# THREE_PHASE_METER.net
KiCad netlist of a schematic drawn in Altium Designer
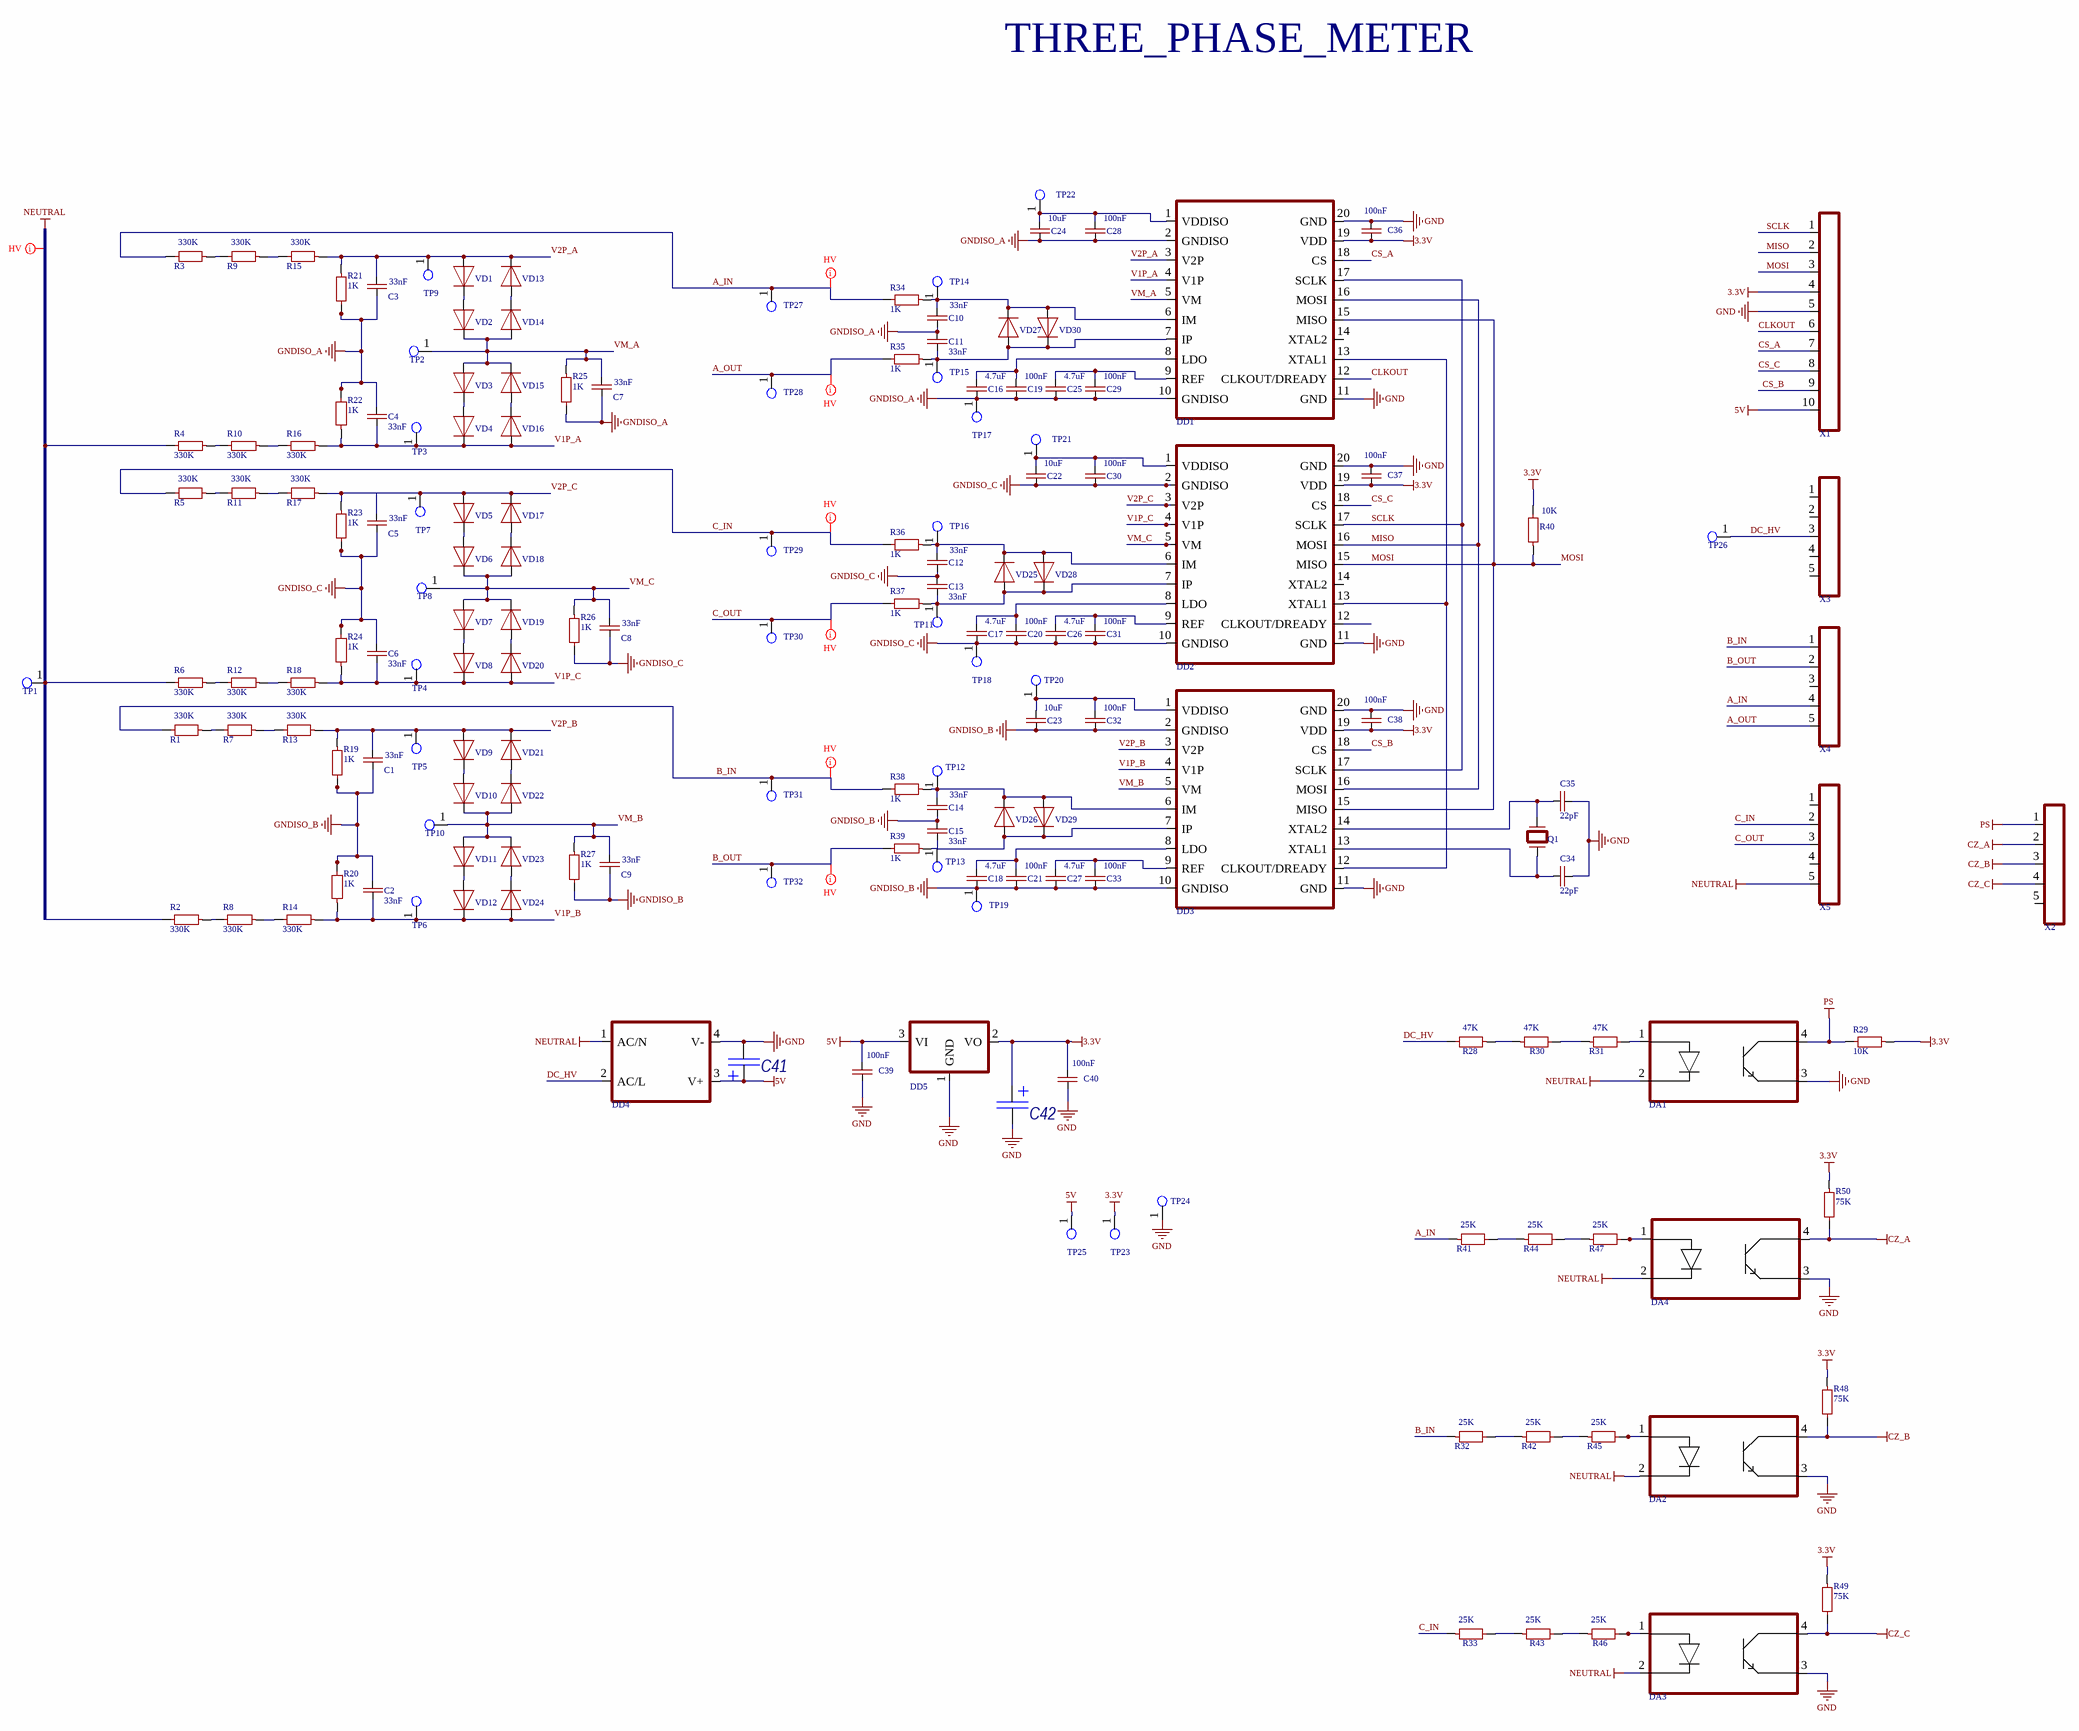
[diagram p0: THREE_PHASE_METER.SchDoc]

(export (version "E")
  (design (tool "Eeschema 10.0.6"))
  (components
    (comp (ref "C1")
      (value "33nF")
      (footprint "CAP-1206")
      (libsource (lib "PASSIVE_COMPONENTS") (part "CAP-NON-POLAR"))
    )
    (comp (ref "C2")
      (value "33nF")
      (footprint "CAP-1206")
      (libsource (lib "PASSIVE_COMPONENTS") (part "CAP-NON-POLAR"))
    )
    (comp (ref "C3")
      (value "33nF")
      (footprint "CAP-1206")
      (libsource (lib "PASSIVE_COMPONENTS") (part "CAP-NON-POLAR"))
    )
    (comp (ref "C4")
      (value "33nF")
      (footprint "CAP-1206")
      (libsource (lib "PASSIVE_COMPONENTS") (part "CAP-NON-POLAR"))
    )
    (comp (ref "C5")
      (value "33nF")
      (footprint "CAP-1206")
      (libsource (lib "PASSIVE_COMPONENTS") (part "CAP-NON-POLAR"))
    )
    (comp (ref "C6")
      (value "33nF")
      (footprint "CAP-1206")
      (libsource (lib "PASSIVE_COMPONENTS") (part "CAP-NON-POLAR"))
    )
    (comp (ref "C7")
      (value "33nF")
      (footprint "CAP-1206")
      (libsource (lib "PASSIVE_COMPONENTS") (part "CAP-NON-POLAR"))
    )
    (comp (ref "C8")
      (value "33nF")
      (footprint "CAP-1206")
      (libsource (lib "PASSIVE_COMPONENTS") (part "CAP-NON-POLAR"))
    )
    (comp (ref "C9")
      (value "33nF")
      (footprint "CAP-1206")
      (libsource (lib "PASSIVE_COMPONENTS") (part "CAP-NON-POLAR"))
    )
    (comp (ref "C10")
      (value "33nF")
      (footprint "CAP-1206")
      (libsource (lib "PASSIVE_COMPONENTS") (part "CAP-NON-POLAR"))
    )
    (comp (ref "C11")
      (value "33nF")
      (footprint "CAP-1206")
      (libsource (lib "PASSIVE_COMPONENTS") (part "CAP-NON-POLAR"))
    )
    (comp (ref "C12")
      (value "33nF")
      (footprint "CAP-1206")
      (libsource (lib "PASSIVE_COMPONENTS") (part "CAP-NON-POLAR"))
    )
    (comp (ref "C13")
      (value "33nF")
      (footprint "CAP-1206")
      (libsource (lib "PASSIVE_COMPONENTS") (part "CAP-NON-POLAR"))
    )
    (comp (ref "C14")
      (value "33nF")
      (footprint "CAP-1206")
      (libsource (lib "PASSIVE_COMPONENTS") (part "CAP-NON-POLAR"))
    )
    (comp (ref "C15")
      (value "33nF")
      (footprint "CAP-1206")
      (libsource (lib "PASSIVE_COMPONENTS") (part "CAP-NON-POLAR"))
    )
    (comp (ref "C16")
      (value "4.7uF")
      (footprint "CAP-1206")
      (libsource (lib "PASSIVE_COMPONENTS") (part "CAP-NON-POLAR"))
    )
    (comp (ref "C17")
      (value "4.7uF")
      (footprint "CAP-1206")
      (libsource (lib "PASSIVE_COMPONENTS") (part "CAP-NON-POLAR"))
    )
    (comp (ref "C18")
      (value "4.7uF")
      (footprint "CAP-1206")
      (libsource (lib "PASSIVE_COMPONENTS") (part "CAP-NON-POLAR"))
    )
    (comp (ref "C19")
      (value "100nF")
      (footprint "CAP-0603")
      (libsource (lib "PASSIVE_COMPONENTS") (part "CAP-NON-POLAR"))
    )
    (comp (ref "C20")
      (value "100nF")
      (footprint "CAP-0603")
      (libsource (lib "PASSIVE_COMPONENTS") (part "CAP-NON-POLAR"))
    )
    (comp (ref "C21")
      (value "100nF")
      (footprint "CAP-0603")
      (libsource (lib "PASSIVE_COMPONENTS") (part "CAP-NON-POLAR"))
    )
    (comp (ref "C22")
      (value "10uF")
      (footprint "CAP-1206")
      (libsource (lib "PASSIVE_COMPONENTS") (part "CAP-NON-POLAR"))
    )
    (comp (ref "C23")
      (value "10uF")
      (footprint "CAP-1206")
      (libsource (lib "PASSIVE_COMPONENTS") (part "CAP-NON-POLAR"))
    )
    (comp (ref "C24")
      (value "10uF")
      (footprint "CAP-1206")
      (libsource (lib "PASSIVE_COMPONENTS") (part "CAP-NON-POLAR"))
    )
    (comp (ref "C25")
      (value "4.7uF")
      (footprint "CAP-1206")
      (libsource (lib "PASSIVE_COMPONENTS") (part "CAP-NON-POLAR"))
    )
    (comp (ref "C26")
      (value "4.7uF")
      (footprint "CAP-1206")
      (libsource (lib "PASSIVE_COMPONENTS") (part "CAP-NON-POLAR"))
    )
    (comp (ref "C27")
      (value "4.7uF")
      (footprint "CAP-1206")
      (libsource (lib "PASSIVE_COMPONENTS") (part "CAP-NON-POLAR"))
    )
    (comp (ref "C28")
      (value "100nF")
      (footprint "CAP-0603")
      (libsource (lib "PASSIVE_COMPONENTS") (part "CAP-NON-POLAR"))
    )
    (comp (ref "C29")
      (value "100nF")
      (footprint "CAP-0603")
      (libsource (lib "PASSIVE_COMPONENTS") (part "CAP-NON-POLAR"))
    )
    (comp (ref "C30")
      (value "100nF")
      (footprint "CAP-0603")
      (libsource (lib "PASSIVE_COMPONENTS") (part "CAP-NON-POLAR"))
    )
    (comp (ref "C31")
      (value "100nF")
      (footprint "CAP-0603")
      (libsource (lib "PASSIVE_COMPONENTS") (part "CAP-NON-POLAR"))
    )
    (comp (ref "C32")
      (value "100nF")
      (footprint "CAP-0603")
      (libsource (lib "PASSIVE_COMPONENTS") (part "CAP-NON-POLAR"))
    )
    (comp (ref "C33")
      (value "100nF")
      (footprint "CAP-0603")
      (libsource (lib "PASSIVE_COMPONENTS") (part "CAP-NON-POLAR"))
    )
    (comp (ref "C34")
      (value "22pF")
      (footprint "CAP-0603")
      (libsource (lib "PASSIVE_COMPONENTS") (part "CAP-NON-POLAR"))
    )
    (comp (ref "C35")
      (value "22pF")
      (footprint "CAP-0603")
      (libsource (lib "PASSIVE_COMPONENTS") (part "CAP-NON-POLAR"))
    )
    (comp (ref "C36")
      (value "100nF")
      (footprint "CAP-0603")
      (libsource (lib "PASSIVE_COMPONENTS") (part "CAP-NON-POLAR"))
    )
    (comp (ref "C37")
      (value "100nF")
      (footprint "CAP-0603")
      (libsource (lib "PASSIVE_COMPONENTS") (part "CAP-NON-POLAR"))
    )
    (comp (ref "C38")
      (value "100nF")
      (footprint "CAP-0603")
      (libsource (lib "PASSIVE_COMPONENTS") (part "CAP-NON-POLAR"))
    )
    (comp (ref "C39")
      (value "100nF")
      (footprint "CAP-0603")
      (libsource (lib "PASSIVE_COMPONENTS") (part "CAP-NON-POLAR"))
    )
    (comp (ref "C40")
      (value "100nF")
      (footprint "CAP-0603")
      (libsource (lib "PASSIVE_COMPONENTS") (part "CAP-NON-POLAR"))
    )
    (comp (ref "C41")
      (value "~")
      (footprint "CAPAE9185X108M")
      (description "Конденсатор электролитический SMD")
      (libsource (lib "Capacitor") (part "CAPAE9185X108M"))
    )
    (comp (ref "C42")
      (value "~")
      (footprint "CAPAE9185X108M")
      (description "Конденсатор электролитический SMD")
      (libsource (lib "Capacitor") (part "CAPAE9185X108M"))
    )
    (comp (ref "DA1") (value "PC817") (footprint "4-SMD") (libsource (lib "PC817") (part "PC817")))
    (comp (ref "DA2") (value "PC817") (footprint "4-SMD") (libsource (lib "PC817") (part "PC817")))
    (comp (ref "DA3") (value "PC817") (footprint "4-SMD") (libsource (lib "PC817") (part "PC817")))
    (comp (ref "DA4") (value "PC817") (footprint "4-SMD") (libsource (lib "PC817") (part "PC817")))
    (comp (ref "DD1") (value "ADE7913") (footprint "SOIC20") (libsource (lib "ADE7913") (part "ADE7913")))
    (comp (ref "DD2") (value "ADE7913") (footprint "SOIC20") (libsource (lib "ADE7913") (part "ADE7913")))
    (comp (ref "DD3") (value "ADE7913") (footprint "SOIC20") (libsource (lib "ADE7913") (part "ADE7913")))
    (comp (ref "DD4") (value "IRM-01") (footprint "IRM-01") (libsource (lib "IRM-01") (part "IRM-01")))
    (comp (ref "DD5") (value "AMS1117") (footprint "SOT-223-3") (libsource (lib "AMS1117") (part "AMS1117")))
    (comp (ref "Q1")
      (value "OSC-2-PIN")
      (footprint "OSC-QSMD12.3x4.5x4.2")
      (libsource (lib "PASSIVE_COMPONENTS") (part "OSC-2-PIN"))
    )
    (comp (ref "R1")
      (value "330K")
      (footprint "RES-1206")
      (libsource (lib "PASSIVE_COMPONENTS") (part "RES-CONST"))
    )
    (comp (ref "R2")
      (value "330K")
      (footprint "RES-1206")
      (libsource (lib "PASSIVE_COMPONENTS") (part "RES-CONST"))
    )
    (comp (ref "R3")
      (value "330K")
      (footprint "RES-1206")
      (libsource (lib "PASSIVE_COMPONENTS") (part "RES-CONST"))
    )
    (comp (ref "R4")
      (value "330K")
      (footprint "RES-1206")
      (libsource (lib "PASSIVE_COMPONENTS") (part "RES-CONST"))
    )
    (comp (ref "R5")
      (value "330K")
      (footprint "RES-1206")
      (libsource (lib "PASSIVE_COMPONENTS") (part "RES-CONST"))
    )
    (comp (ref "R6")
      (value "330K")
      (footprint "RES-1206")
      (libsource (lib "PASSIVE_COMPONENTS") (part "RES-CONST"))
    )
    (comp (ref "R7")
      (value "330K")
      (footprint "RES-1206")
      (libsource (lib "PASSIVE_COMPONENTS") (part "RES-CONST"))
    )
    (comp (ref "R8")
      (value "330K")
      (footprint "RES-1206")
      (libsource (lib "PASSIVE_COMPONENTS") (part "RES-CONST"))
    )
    (comp (ref "R9")
      (value "330K")
      (footprint "RES-1206")
      (libsource (lib "PASSIVE_COMPONENTS") (part "RES-CONST"))
    )
    (comp (ref "R10")
      (value "330K")
      (footprint "RES-1206")
      (libsource (lib "PASSIVE_COMPONENTS") (part "RES-CONST"))
    )
    (comp (ref "R11")
      (value "330K")
      (footprint "RES-1206")
      (libsource (lib "PASSIVE_COMPONENTS") (part "RES-CONST"))
    )
    (comp (ref "R12")
      (value "330K")
      (footprint "RES-1206")
      (libsource (lib "PASSIVE_COMPONENTS") (part "RES-CONST"))
    )
    (comp (ref "R13")
      (value "330K")
      (footprint "RES-1206")
      (libsource (lib "PASSIVE_COMPONENTS") (part "RES-CONST"))
    )
    (comp (ref "R14")
      (value "330K")
      (footprint "RES-1206")
      (libsource (lib "PASSIVE_COMPONENTS") (part "RES-CONST"))
    )
    (comp (ref "R15")
      (value "330K")
      (footprint "RES-1206")
      (libsource (lib "PASSIVE_COMPONENTS") (part "RES-CONST"))
    )
    (comp (ref "R16")
      (value "330K")
      (footprint "RES-1206")
      (libsource (lib "PASSIVE_COMPONENTS") (part "RES-CONST"))
    )
    (comp (ref "R17")
      (value "330K")
      (footprint "RES-1206")
      (libsource (lib "PASSIVE_COMPONENTS") (part "RES-CONST"))
    )
    (comp (ref "R18")
      (value "330K")
      (footprint "RES-1206")
      (libsource (lib "PASSIVE_COMPONENTS") (part "RES-CONST"))
    )
    (comp (ref "R19")
      (value "1K")
      (footprint "RES-1206")
      (libsource (lib "PASSIVE_COMPONENTS") (part "RES-CONST"))
    )
    (comp (ref "R20")
      (value "1K")
      (footprint "RES-1206")
      (libsource (lib "PASSIVE_COMPONENTS") (part "RES-CONST"))
    )
    (comp (ref "R21")
      (value "1K")
      (footprint "RES-1206")
      (libsource (lib "PASSIVE_COMPONENTS") (part "RES-CONST"))
    )
    (comp (ref "R22")
      (value "1K")
      (footprint "RES-1206")
      (libsource (lib "PASSIVE_COMPONENTS") (part "RES-CONST"))
    )
    (comp (ref "R23")
      (value "1K")
      (footprint "RES-1206")
      (libsource (lib "PASSIVE_COMPONENTS") (part "RES-CONST"))
    )
    (comp (ref "R24")
      (value "1K")
      (footprint "RES-1206")
      (libsource (lib "PASSIVE_COMPONENTS") (part "RES-CONST"))
    )
    (comp (ref "R25")
      (value "1K")
      (footprint "RES-1206")
      (libsource (lib "PASSIVE_COMPONENTS") (part "RES-CONST"))
    )
    (comp (ref "R26")
      (value "1K")
      (footprint "RES-1206")
      (libsource (lib "PASSIVE_COMPONENTS") (part "RES-CONST"))
    )
    (comp (ref "R27")
      (value "1K")
      (footprint "RES-1206")
      (libsource (lib "PASSIVE_COMPONENTS") (part "RES-CONST"))
    )
    (comp (ref "R28")
      (value "47K")
      (footprint "RES-1206")
      (libsource (lib "PASSIVE_COMPONENTS") (part "RES-CONST"))
    )
    (comp (ref "R29")
      (value "10K")
      (footprint "RES-0603")
      (libsource (lib "PASSIVE_COMPONENTS") (part "RES-CONST"))
    )
    (comp (ref "R30")
      (value "47K")
      (footprint "RES-1206")
      (libsource (lib "PASSIVE_COMPONENTS") (part "RES-CONST"))
    )
    (comp (ref "R31")
      (value "47K")
      (footprint "RES-1206")
      (libsource (lib "PASSIVE_COMPONENTS") (part "RES-CONST"))
    )
    (comp (ref "R32")
      (value "25K")
      (footprint "RES-1206")
      (libsource (lib "PASSIVE_COMPONENTS") (part "RES-CONST"))
    )
    (comp (ref "R33")
      (value "25K")
      (footprint "RES-1206")
      (libsource (lib "PASSIVE_COMPONENTS") (part "RES-CONST"))
    )
    (comp (ref "R34")
      (value "1K")
      (footprint "RES-1206")
      (libsource (lib "PASSIVE_COMPONENTS") (part "RES-CONST"))
    )
    (comp (ref "R35")
      (value "1K")
      (footprint "RES-1206")
      (libsource (lib "PASSIVE_COMPONENTS") (part "RES-CONST"))
    )
    (comp (ref "R36")
      (value "1K")
      (footprint "RES-1206")
      (libsource (lib "PASSIVE_COMPONENTS") (part "RES-CONST"))
    )
    (comp (ref "R37")
      (value "1K")
      (footprint "RES-1206")
      (libsource (lib "PASSIVE_COMPONENTS") (part "RES-CONST"))
    )
    (comp (ref "R38")
      (value "1K")
      (footprint "RES-1206")
      (libsource (lib "PASSIVE_COMPONENTS") (part "RES-CONST"))
    )
    (comp (ref "R39")
      (value "1K")
      (footprint "RES-1206")
      (libsource (lib "PASSIVE_COMPONENTS") (part "RES-CONST"))
    )
    (comp (ref "R40")
      (value "10K")
      (footprint "RES-0603")
      (libsource (lib "PASSIVE_COMPONENTS") (part "RES-CONST"))
    )
    (comp (ref "R41")
      (value "25K")
      (footprint "RES-1206")
      (libsource (lib "PASSIVE_COMPONENTS") (part "RES-CONST"))
    )
    (comp (ref "R42")
      (value "25K")
      (footprint "RES-1206")
      (libsource (lib "PASSIVE_COMPONENTS") (part "RES-CONST"))
    )
    (comp (ref "R43")
      (value "25K")
      (footprint "RES-1206")
      (libsource (lib "PASSIVE_COMPONENTS") (part "RES-CONST"))
    )
    (comp (ref "R44")
      (value "25K")
      (footprint "RES-1206")
      (libsource (lib "PASSIVE_COMPONENTS") (part "RES-CONST"))
    )
    (comp (ref "R45")
      (value "25K")
      (footprint "RES-1206")
      (libsource (lib "PASSIVE_COMPONENTS") (part "RES-CONST"))
    )
    (comp (ref "R46")
      (value "25K")
      (footprint "RES-1206")
      (libsource (lib "PASSIVE_COMPONENTS") (part "RES-CONST"))
    )
    (comp (ref "R47")
      (value "25K")
      (footprint "RES-1206")
      (libsource (lib "PASSIVE_COMPONENTS") (part "RES-CONST"))
    )
    (comp (ref "R48")
      (value "75K")
      (footprint "RES-0603")
      (libsource (lib "PASSIVE_COMPONENTS") (part "RES-CONST"))
    )
    (comp (ref "R49")
      (value "75K")
      (footprint "RES-0603")
      (libsource (lib "PASSIVE_COMPONENTS") (part "RES-CONST"))
    )
    (comp (ref "R50")
      (value "75K")
      (footprint "RES-0603")
      (libsource (lib "PASSIVE_COMPONENTS") (part "RES-CONST"))
    )
    (comp (ref "TP1")
      (value "Test_Point_PCB")
      (footprint "Test_Point")
      (description "Test_Point")
      (libsource (lib "Test_Point") (part "TP_PCB?"))
    )
    (comp (ref "TP2")
      (value "Test_Point_PCB")
      (footprint "Test_Point")
      (description "Test_Point")
      (libsource (lib "Test_Point") (part "TP_PCB?"))
    )
    (comp (ref "TP3")
      (value "Test_Point_PCB")
      (footprint "Test_Point")
      (description "Test_Point")
      (libsource (lib "Test_Point") (part "TP_PCB?"))
    )
    (comp (ref "TP4")
      (value "Test_Point_PCB")
      (footprint "Test_Point")
      (description "Test_Point")
      (libsource (lib "Test_Point") (part "TP_PCB?"))
    )
    (comp (ref "TP5")
      (value "Test_Point_PCB")
      (footprint "Test_Point")
      (description "Test_Point")
      (libsource (lib "Test_Point") (part "TP_PCB?"))
    )
    (comp (ref "TP6")
      (value "Test_Point_PCB")
      (footprint "Test_Point")
      (description "Test_Point")
      (libsource (lib "Test_Point") (part "TP_PCB?"))
    )
    (comp (ref "TP7")
      (value "Test_Point_PCB")
      (footprint "Test_Point")
      (description "Test_Point")
      (libsource (lib "Test_Point") (part "TP_PCB?"))
    )
    (comp (ref "TP8")
      (value "Test_Point_PCB")
      (footprint "Test_Point")
      (description "Test_Point")
      (libsource (lib "Test_Point") (part "TP_PCB?"))
    )
    (comp (ref "TP9")
      (value "Test_Point_PCB")
      (footprint "Test_Point")
      (description "Test_Point")
      (libsource (lib "Test_Point") (part "TP_PCB?"))
    )
    (comp (ref "TP10")
      (value "Test_Point_PCB")
      (footprint "Test_Point")
      (description "Test_Point")
      (libsource (lib "Test_Point") (part "TP_PCB?"))
    )
    (comp (ref "TP11")
      (value "Test_Point_PCB")
      (footprint "Test_Point")
      (description "Test_Point")
      (libsource (lib "Test_Point") (part "TP_PCB?"))
    )
    (comp (ref "TP12")
      (value "Test_Point_PCB")
      (footprint "Test_Point")
      (description "Test_Point")
      (libsource (lib "Test_Point") (part "TP_PCB?"))
    )
    (comp (ref "TP13")
      (value "Test_Point_PCB")
      (footprint "Test_Point")
      (description "Test_Point")
      (libsource (lib "Test_Point") (part "TP_PCB?"))
    )
    (comp (ref "TP14")
      (value "Test_Point_PCB")
      (footprint "Test_Point")
      (description "Test_Point")
      (libsource (lib "Test_Point") (part "TP_PCB?"))
    )
    (comp (ref "TP15")
      (value "Test_Point_PCB")
      (footprint "Test_Point")
      (description "Test_Point")
      (libsource (lib "Test_Point") (part "TP_PCB?"))
    )
    (comp (ref "TP16")
      (value "Test_Point_PCB")
      (footprint "Test_Point")
      (description "Test_Point")
      (libsource (lib "Test_Point") (part "TP_PCB?"))
    )
    (comp (ref "TP17")
      (value "Test_Point_PCB")
      (footprint "Test_Point")
      (description "Test_Point")
      (libsource (lib "Test_Point") (part "TP_PCB?"))
    )
    (comp (ref "TP18")
      (value "Test_Point_PCB")
      (footprint "Test_Point")
      (description "Test_Point")
      (libsource (lib "Test_Point") (part "TP_PCB?"))
    )
    (comp (ref "TP19")
      (value "Test_Point_PCB")
      (footprint "Test_Point")
      (description "Test_Point")
      (libsource (lib "Test_Point") (part "TP_PCB?"))
    )
    (comp (ref "TP20")
      (value "Test_Point_PCB")
      (footprint "Test_Point")
      (description "Test_Point")
      (libsource (lib "Test_Point") (part "TP_PCB?"))
    )
    (comp (ref "TP21")
      (value "Test_Point_PCB")
      (footprint "Test_Point")
      (description "Test_Point")
      (libsource (lib "Test_Point") (part "TP_PCB?"))
    )
    (comp (ref "TP22")
      (value "Test_Point_PCB")
      (footprint "Test_Point")
      (description "Test_Point")
      (libsource (lib "Test_Point") (part "TP_PCB?"))
    )
    (comp (ref "TP23")
      (value "Test_Point_PCB")
      (footprint "Test_Point")
      (description "Test_Point")
      (libsource (lib "Test_Point") (part "TP_PCB?"))
    )
    (comp (ref "TP24")
      (value "Test_Point_PCB")
      (footprint "Test_Point")
      (description "Test_Point")
      (libsource (lib "Test_Point") (part "TP_PCB?"))
    )
    (comp (ref "TP25")
      (value "Test_Point_PCB")
      (footprint "Test_Point")
      (description "Test_Point")
      (libsource (lib "Test_Point") (part "TP_PCB?"))
    )
    (comp (ref "TP26")
      (value "Test_Point_PCB")
      (footprint "Test_Point")
      (description "Test_Point")
      (libsource (lib "Test_Point") (part "TP_PCB?"))
    )
    (comp (ref "TP27")
      (value "Test_Point_PCB")
      (footprint "Test_Point")
      (description "Test_Point")
      (libsource (lib "Test_Point") (part "TP_PCB?"))
    )
    (comp (ref "TP28")
      (value "Test_Point_PCB")
      (footprint "Test_Point")
      (description "Test_Point")
      (libsource (lib "Test_Point") (part "TP_PCB?"))
    )
    (comp (ref "TP29")
      (value "Test_Point_PCB")
      (footprint "Test_Point")
      (description "Test_Point")
      (libsource (lib "Test_Point") (part "TP_PCB?"))
    )
    (comp (ref "TP30")
      (value "Test_Point_PCB")
      (footprint "Test_Point")
      (description "Test_Point")
      (libsource (lib "Test_Point") (part "TP_PCB?"))
    )
    (comp (ref "TP31")
      (value "Test_Point_PCB")
      (footprint "Test_Point")
      (description "Test_Point")
      (libsource (lib "Test_Point") (part "TP_PCB?"))
    )
    (comp (ref "TP32")
      (value "Test_Point_PCB")
      (footprint "Test_Point")
      (description "Test_Point")
      (libsource (lib "Test_Point") (part "TP_PCB?"))
    )
    (comp (ref "VD1")
      (value "DIODE")
      (footprint "DIODE-0805")
      (libsource (lib "PASSIVE_COMPONENTS") (part "DIODE"))
    )
    (comp (ref "VD2")
      (value "DIODE")
      (footprint "DIODE-0805")
      (libsource (lib "PASSIVE_COMPONENTS") (part "DIODE"))
    )
    (comp (ref "VD3")
      (value "DIODE")
      (footprint "DIODE-0805")
      (libsource (lib "PASSIVE_COMPONENTS") (part "DIODE"))
    )
    (comp (ref "VD4")
      (value "DIODE")
      (footprint "DIODE-0805")
      (libsource (lib "PASSIVE_COMPONENTS") (part "DIODE"))
    )
    (comp (ref "VD5")
      (value "DIODE")
      (footprint "DIODE-0805")
      (libsource (lib "PASSIVE_COMPONENTS") (part "DIODE"))
    )
    (comp (ref "VD6")
      (value "DIODE")
      (footprint "DIODE-0805")
      (libsource (lib "PASSIVE_COMPONENTS") (part "DIODE"))
    )
    (comp (ref "VD7")
      (value "DIODE")
      (footprint "DIODE-0805")
      (libsource (lib "PASSIVE_COMPONENTS") (part "DIODE"))
    )
    (comp (ref "VD8")
      (value "DIODE")
      (footprint "DIODE-0805")
      (libsource (lib "PASSIVE_COMPONENTS") (part "DIODE"))
    )
    (comp (ref "VD9")
      (value "DIODE")
      (footprint "DIODE-0805")
      (libsource (lib "PASSIVE_COMPONENTS") (part "DIODE"))
    )
    (comp (ref "VD10")
      (value "DIODE")
      (footprint "DIODE-0805")
      (libsource (lib "PASSIVE_COMPONENTS") (part "DIODE"))
    )
    (comp (ref "VD11")
      (value "DIODE")
      (footprint "DIODE-0805")
      (libsource (lib "PASSIVE_COMPONENTS") (part "DIODE"))
    )
    (comp (ref "VD12")
      (value "DIODE")
      (footprint "DIODE-0805")
      (libsource (lib "PASSIVE_COMPONENTS") (part "DIODE"))
    )
    (comp (ref "VD13")
      (value "DIODE")
      (footprint "DIODE-0805")
      (libsource (lib "PASSIVE_COMPONENTS") (part "DIODE"))
    )
    (comp (ref "VD14")
      (value "DIODE")
      (footprint "DIODE-0805")
      (libsource (lib "PASSIVE_COMPONENTS") (part "DIODE"))
    )
    (comp (ref "VD15")
      (value "DIODE")
      (footprint "DIODE-0805")
      (libsource (lib "PASSIVE_COMPONENTS") (part "DIODE"))
    )
    (comp (ref "VD16")
      (value "DIODE")
      (footprint "DIODE-0805")
      (libsource (lib "PASSIVE_COMPONENTS") (part "DIODE"))
    )
    (comp (ref "VD17")
      (value "DIODE")
      (footprint "DIODE-0805")
      (libsource (lib "PASSIVE_COMPONENTS") (part "DIODE"))
    )
    (comp (ref "VD18")
      (value "DIODE")
      (footprint "DIODE-0805")
      (libsource (lib "PASSIVE_COMPONENTS") (part "DIODE"))
    )
    (comp (ref "VD19")
      (value "DIODE")
      (footprint "DIODE-0805")
      (libsource (lib "PASSIVE_COMPONENTS") (part "DIODE"))
    )
    (comp (ref "VD20")
      (value "DIODE")
      (footprint "DIODE-0805")
      (libsource (lib "PASSIVE_COMPONENTS") (part "DIODE"))
    )
    (comp (ref "VD21")
      (value "DIODE")
      (footprint "DIODE-0805")
      (libsource (lib "PASSIVE_COMPONENTS") (part "DIODE"))
    )
    (comp (ref "VD22")
      (value "DIODE")
      (footprint "DIODE-0805")
      (libsource (lib "PASSIVE_COMPONENTS") (part "DIODE"))
    )
    (comp (ref "VD23")
      (value "DIODE")
      (footprint "DIODE-0805")
      (libsource (lib "PASSIVE_COMPONENTS") (part "DIODE"))
    )
    (comp (ref "VD24")
      (value "DIODE")
      (footprint "DIODE-0805")
      (libsource (lib "PASSIVE_COMPONENTS") (part "DIODE"))
    )
    (comp (ref "VD25")
      (value "DIODE")
      (footprint "DIODE-0805")
      (libsource (lib "PASSIVE_COMPONENTS") (part "DIODE"))
    )
    (comp (ref "VD26")
      (value "DIODE")
      (footprint "DIODE-0805")
      (libsource (lib "PASSIVE_COMPONENTS") (part "DIODE"))
    )
    (comp (ref "VD27")
      (value "DIODE")
      (footprint "DIODE-0805")
      (libsource (lib "PASSIVE_COMPONENTS") (part "DIODE"))
    )
    (comp (ref "VD28")
      (value "DIODE")
      (footprint "DIODE-0805")
      (libsource (lib "PASSIVE_COMPONENTS") (part "DIODE"))
    )
    (comp (ref "VD29")
      (value "DIODE")
      (footprint "DIODE-0805")
      (libsource (lib "PASSIVE_COMPONENTS") (part "DIODE"))
    )
    (comp (ref "VD30")
      (value "DIODE")
      (footprint "DIODE-0805")
      (libsource (lib "PASSIVE_COMPONENTS") (part "DIODE"))
    )
    (comp (ref "X1") (value "BH-10") (footprint "BH-10") (libsource (lib "BH-10") (part "BH-10")))
    (comp (ref "X2")
      (value "CONN-5-PIN")
      (footprint "CONN-PLS-5-2.54_2")
      (libsource (lib "PLS-5__") (part "CONN-5-PIN"))
    )
    (comp (ref "X3")
      (value "CONN-5-PIN")
      (footprint "CONN-PLS-5-2.54_2")
      (libsource (lib "PLS-5__") (part "CONN-5-PIN"))
    )
    (comp (ref "X4")
      (value "CONN-5-PIN")
      (footprint "CONN-PLS-5-2.54_2")
      (libsource (lib "PLS-5__") (part "CONN-5-PIN"))
    )
    (comp (ref "X5")
      (value "CONN-5-PIN")
      (footprint "CONN-PLS-5-2.54_2")
      (libsource (lib "PLS-5__") (part "CONN-5-PIN"))
    )
  )
  (nets
    (net (code "1") (name "/A_IN") (class "Default")
      (node (ref "R3") (pin "2") (pinfunction "2_2") (pintype "passive"))
      (node (ref "R34") (pin "2") (pinfunction "2_2") (pintype "passive"))
      (node (ref "R41") (pin "1") (pinfunction "1_1") (pintype "passive"))
      (node (ref "TP27") (pin "1") (pinfunction "G9_1") (pintype "passive"))
      (node (ref "X4") (pin "4") (pinfunction "4_4") (pintype "passive"))
    )
    (net (code "2") (name "/A_OUT") (class "Default")
      (node (ref "R35") (pin "2") (pinfunction "2_2") (pintype "passive"))
      (node (ref "TP28") (pin "1") (pinfunction "G9_1") (pintype "passive"))
      (node (ref "X4") (pin "5") (pinfunction "5_5") (pintype "passive"))
    )
    (net (code "3") (name "/B_IN") (class "Default")
      (node (ref "R1") (pin "2") (pinfunction "2_2") (pintype "passive"))
      (node (ref "R32") (pin "1") (pinfunction "1_1") (pintype "passive"))
      (node (ref "R38") (pin "2") (pinfunction "2_2") (pintype "passive"))
      (node (ref "TP31") (pin "1") (pinfunction "G9_1") (pintype "passive"))
      (node (ref "X4") (pin "1") (pinfunction "1_1") (pintype "passive"))
    )
    (net (code "4") (name "/B_OUT") (class "Default")
      (node (ref "R39") (pin "2") (pinfunction "2_2") (pintype "passive"))
      (node (ref "TP32") (pin "1") (pinfunction "G9_1") (pintype "passive"))
      (node (ref "X4") (pin "2") (pinfunction "2_2") (pintype "passive"))
    )
    (net (code "5") (name "/CLKOUT") (class "Default")
      (node (ref "DD1") (pin "12") (pinfunction "CLKOUT/DREADY_12") (pintype "passive"))
      (node (ref "X1") (pin "6") (pinfunction "6_6") (pintype "passive"))
    )
    (net (code "6") (name "/CS_A") (class "Default")
      (node (ref "DD1") (pin "18") (pinfunction "CS_18") (pintype "passive"))
      (node (ref "X1") (pin "7") (pinfunction "7_7") (pintype "passive"))
    )
    (net (code "7") (name "/CS_B") (class "Default")
      (node (ref "DD3") (pin "18") (pinfunction "CS_18") (pintype "passive"))
      (node (ref "X1") (pin "9") (pinfunction "9_9") (pintype "passive"))
    )
    (net (code "8") (name "/CS_C") (class "Default")
      (node (ref "DD2") (pin "18") (pinfunction "CS_18") (pintype "passive"))
      (node (ref "X1") (pin "8") (pinfunction "8_8") (pintype "passive"))
    )
    (net (code "9") (name "/C_IN") (class "Default")
      (node (ref "R33") (pin "1") (pinfunction "1_1") (pintype "passive"))
      (node (ref "R36") (pin "2") (pinfunction "2_2") (pintype "passive"))
      (node (ref "R5") (pin "2") (pinfunction "2_2") (pintype "passive"))
      (node (ref "TP29") (pin "1") (pinfunction "G9_1") (pintype "passive"))
      (node (ref "X5") (pin "2") (pinfunction "2_2") (pintype "passive"))
    )
    (net (code "10") (name "/C_OUT") (class "Default")
      (node (ref "R37") (pin "2") (pinfunction "2_2") (pintype "passive"))
      (node (ref "TP30") (pin "1") (pinfunction "G9_1") (pintype "passive"))
      (node (ref "X5") (pin "3") (pinfunction "3_3") (pintype "passive"))
    )
    (net (code "11") (name "/DC_HV") (class "Default")
      (node (ref "DD4") (pin "2") (pinfunction "AC/L_2") (pintype "passive"))
      (node (ref "R28") (pin "2") (pinfunction "2_2") (pintype "passive"))
      (node (ref "TP26") (pin "1") (pinfunction "G9_1") (pintype "passive"))
      (node (ref "X3") (pin "3") (pinfunction "3_3") (pintype "passive"))
    )
    (net (code "12") (name "/MISO") (class "Default")
      (node (ref "DD1") (pin "16") (pinfunction "MOSI_16") (pintype "passive"))
      (node (ref "DD2") (pin "16") (pinfunction "MOSI_16") (pintype "passive"))
      (node (ref "DD3") (pin "16") (pinfunction "MOSI_16") (pintype "passive"))
      (node (ref "X1") (pin "2") (pinfunction "2_2") (pintype "passive"))
    )
    (net (code "13") (name "/MOSI") (class "Default")
      (node (ref "DD1") (pin "15") (pinfunction "MISO_15") (pintype "passive"))
      (node (ref "DD2") (pin "15") (pinfunction "MISO_15") (pintype "passive"))
      (node (ref "DD3") (pin "15") (pinfunction "MISO_15") (pintype "passive"))
      (node (ref "R40") (pin "1") (pinfunction "1_1") (pintype "passive"))
      (node (ref "X1") (pin "3") (pinfunction "3_3") (pintype "passive"))
    )
    (net (code "14") (name "/SCLK") (class "Default")
      (node (ref "DD1") (pin "17") (pinfunction "_SCLK_17") (pintype "passive"))
      (node (ref "DD2") (pin "17") (pinfunction "_SCLK_17") (pintype "passive"))
      (node (ref "DD3") (pin "17") (pinfunction "_SCLK_17") (pintype "passive"))
      (node (ref "X1") (pin "1") (pinfunction "1_1") (pintype "passive"))
    )
    (net (code "15") (name "/V1P_A") (class "Default")
      (node (ref "C4") (pin "2") (pinfunction "2_2") (pintype "passive"))
      (node (ref "DD1") (pin "4") (pinfunction "V1P_4") (pintype "passive"))
      (node (ref "R16") (pin "1") (pinfunction "1_1") (pintype "passive"))
      (node (ref "R22") (pin "1") (pinfunction "1_1") (pintype "passive"))
      (node (ref "TP3") (pin "1") (pinfunction "G9_1") (pintype "passive"))
      (node (ref "VD16") (pin "2") (pinfunction "A_2") (pintype "passive"))
      (node (ref "VD4") (pin "1") (pinfunction "C_1") (pintype "passive"))
    )
    (net (code "16") (name "/V1P_B") (class "Default")
      (node (ref "C2") (pin "2") (pinfunction "2_2") (pintype "passive"))
      (node (ref "DD3") (pin "4") (pinfunction "V1P_4") (pintype "passive"))
      (node (ref "R14") (pin "1") (pinfunction "1_1") (pintype "passive"))
      (node (ref "R20") (pin "1") (pinfunction "1_1") (pintype "passive"))
      (node (ref "TP6") (pin "1") (pinfunction "G9_1") (pintype "passive"))
      (node (ref "VD12") (pin "1") (pinfunction "C_1") (pintype "passive"))
      (node (ref "VD24") (pin "2") (pinfunction "A_2") (pintype "passive"))
    )
    (net (code "17") (name "/V1P_C") (class "Default")
      (node (ref "C6") (pin "2") (pinfunction "2_2") (pintype "passive"))
      (node (ref "DD2") (pin "4") (pinfunction "V1P_4") (pintype "passive"))
      (node (ref "R18") (pin "1") (pinfunction "1_1") (pintype "passive"))
      (node (ref "R24") (pin "1") (pinfunction "1_1") (pintype "passive"))
      (node (ref "TP4") (pin "1") (pinfunction "G9_1") (pintype "passive"))
      (node (ref "VD20") (pin "2") (pinfunction "A_2") (pintype "passive"))
      (node (ref "VD8") (pin "1") (pinfunction "C_1") (pintype "passive"))
    )
    (net (code "18") (name "/V2P_A") (class "Default")
      (node (ref "C3") (pin "2") (pinfunction "2_2") (pintype "passive"))
      (node (ref "DD1") (pin "3") (pinfunction "V2P_3") (pintype "passive"))
      (node (ref "R15") (pin "1") (pinfunction "1_1") (pintype "passive"))
      (node (ref "R21") (pin "1") (pinfunction "1_1") (pintype "passive"))
      (node (ref "TP9") (pin "1") (pinfunction "G9_1") (pintype "passive"))
      (node (ref "VD1") (pin "2") (pinfunction "A_2") (pintype "passive"))
      (node (ref "VD13") (pin "1") (pinfunction "C_1") (pintype "passive"))
    )
    (net (code "19") (name "/V2P_B") (class "Default")
      (node (ref "C1") (pin "2") (pinfunction "2_2") (pintype "passive"))
      (node (ref "DD3") (pin "3") (pinfunction "V2P_3") (pintype "passive"))
      (node (ref "R13") (pin "1") (pinfunction "1_1") (pintype "passive"))
      (node (ref "R19") (pin "1") (pinfunction "1_1") (pintype "passive"))
      (node (ref "TP5") (pin "1") (pinfunction "G9_1") (pintype "passive"))
      (node (ref "VD21") (pin "1") (pinfunction "C_1") (pintype "passive"))
      (node (ref "VD9") (pin "2") (pinfunction "A_2") (pintype "passive"))
    )
    (net (code "20") (name "/V2P_C") (class "Default")
      (node (ref "C5") (pin "2") (pinfunction "2_2") (pintype "passive"))
      (node (ref "DD2") (pin "3") (pinfunction "V2P_3") (pintype "passive"))
      (node (ref "R17") (pin "1") (pinfunction "1_1") (pintype "passive"))
      (node (ref "R23") (pin "1") (pinfunction "1_1") (pintype "passive"))
      (node (ref "TP7") (pin "1") (pinfunction "G9_1") (pintype "passive"))
      (node (ref "VD17") (pin "1") (pinfunction "C_1") (pintype "passive"))
      (node (ref "VD5") (pin "2") (pinfunction "A_2") (pintype "passive"))
    )
    (net (code "21") (name "/VM_A") (class "Default")
      (node (ref "C7") (pin "2") (pinfunction "2_2") (pintype "passive"))
      (node (ref "DD1") (pin "5") (pinfunction "VM_5") (pintype "passive"))
      (node (ref "R25") (pin "1") (pinfunction "1_1") (pintype "passive"))
      (node (ref "TP2") (pin "1") (pinfunction "G9_1") (pintype "passive"))
      (node (ref "VD14") (pin "2") (pinfunction "A_2") (pintype "passive"))
      (node (ref "VD15") (pin "1") (pinfunction "C_1") (pintype "passive"))
      (node (ref "VD2") (pin "1") (pinfunction "C_1") (pintype "passive"))
      (node (ref "VD3") (pin "2") (pinfunction "A_2") (pintype "passive"))
    )
    (net (code "22") (name "/VM_B") (class "Default")
      (node (ref "C9") (pin "2") (pinfunction "2_2") (pintype "passive"))
      (node (ref "DD3") (pin "5") (pinfunction "VM_5") (pintype "passive"))
      (node (ref "R27") (pin "1") (pinfunction "1_1") (pintype "passive"))
      (node (ref "TP10") (pin "1") (pinfunction "G9_1") (pintype "passive"))
      (node (ref "VD10") (pin "1") (pinfunction "C_1") (pintype "passive"))
      (node (ref "VD11") (pin "2") (pinfunction "A_2") (pintype "passive"))
      (node (ref "VD22") (pin "2") (pinfunction "A_2") (pintype "passive"))
      (node (ref "VD23") (pin "1") (pinfunction "C_1") (pintype "passive"))
    )
    (net (code "23") (name "/VM_C") (class "Default")
      (node (ref "C8") (pin "2") (pinfunction "2_2") (pintype "passive"))
      (node (ref "DD2") (pin "5") (pinfunction "VM_5") (pintype "passive"))
      (node (ref "R26") (pin "1") (pinfunction "1_1") (pintype "passive"))
      (node (ref "TP8") (pin "1") (pinfunction "G9_1") (pintype "passive"))
      (node (ref "VD18") (pin "2") (pinfunction "A_2") (pintype "passive"))
      (node (ref "VD19") (pin "1") (pinfunction "C_1") (pintype "passive"))
      (node (ref "VD6") (pin "1") (pinfunction "C_1") (pintype "passive"))
      (node (ref "VD7") (pin "2") (pinfunction "A_2") (pintype "passive"))
    )
    (net (code "24") (name "3.3V") (class "Default")
      (node (ref "C36") (pin "1") (pinfunction "1_1") (pintype "passive"))
      (node (ref "C37") (pin "1") (pinfunction "1_1") (pintype "passive"))
      (node (ref "C38") (pin "1") (pinfunction "1_1") (pintype "passive"))
      (node (ref "C40") (pin "2") (pinfunction "2_2") (pintype "passive"))
      (node (ref "C42") (pin "1") (pinfunction "+_1") (pintype "passive"))
      (node (ref "DD1") (pin "19") (pinfunction "VDD_19") (pintype "passive"))
      (node (ref "DD2") (pin "19") (pinfunction "VDD_19") (pintype "passive"))
      (node (ref "DD3") (pin "19") (pinfunction "VDD_19") (pintype "passive"))
      (node (ref "DD5") (pin "2") (pinfunction "VO_2") (pintype "passive"))
      (node (ref "R29") (pin "1") (pinfunction "1_1") (pintype "passive"))
      (node (ref "R40") (pin "2") (pinfunction "2_2") (pintype "passive"))
      (node (ref "R48") (pin "1") (pinfunction "1_1") (pintype "passive"))
      (node (ref "R49") (pin "1") (pinfunction "1_1") (pintype "passive"))
      (node (ref "R50") (pin "1") (pinfunction "1_1") (pintype "passive"))
      (node (ref "TP23") (pin "1") (pinfunction "G9_1") (pintype "passive"))
      (node (ref "X1") (pin "4") (pinfunction "4_4") (pintype "passive"))
    )
    (net (code "25") (name "5V") (class "Default")
      (node (ref "C39") (pin "2") (pinfunction "2_2") (pintype "passive"))
      (node (ref "C41") (pin "1") (pinfunction "+_1") (pintype "passive"))
      (node (ref "DD4") (pin "3") (pinfunction "V+_3") (pintype "passive"))
      (node (ref "DD5") (pin "3") (pinfunction "VI_3") (pintype "passive"))
      (node (ref "TP25") (pin "1") (pinfunction "G9_1") (pintype "passive"))
      (node (ref "X1") (pin "10") (pinfunction "10_10") (pintype "passive"))
    )
    (net (code "26") (name "CZ_A") (class "Default")
      (node (ref "DA4") (pin "4") (pinfunction "COLLECTOR_4") (pintype "passive"))
      (node (ref "R50") (pin "2") (pinfunction "2_2") (pintype "passive"))
      (node (ref "X2") (pin "2") (pinfunction "2_2") (pintype "passive"))
    )
    (net (code "27") (name "CZ_B") (class "Default")
      (node (ref "DA2") (pin "4") (pinfunction "COLLECTOR_4") (pintype "passive"))
      (node (ref "R48") (pin "2") (pinfunction "2_2") (pintype "passive"))
      (node (ref "X2") (pin "3") (pinfunction "3_3") (pintype "passive"))
    )
    (net (code "28") (name "CZ_C") (class "Default")
      (node (ref "DA3") (pin "4") (pinfunction "COLLECTOR_4") (pintype "passive"))
      (node (ref "R49") (pin "2") (pinfunction "2_2") (pintype "passive"))
      (node (ref "X2") (pin "4") (pinfunction "4_4") (pintype "passive"))
    )
    (net (code "29") (name "GND") (class "Default")
      (node (ref "C34") (pin "1") (pinfunction "1_1") (pintype "passive"))
      (node (ref "C35") (pin "1") (pinfunction "1_1") (pintype "passive"))
      (node (ref "C36") (pin "2") (pinfunction "2_2") (pintype "passive"))
      (node (ref "C37") (pin "2") (pinfunction "2_2") (pintype "passive"))
      (node (ref "C38") (pin "2") (pinfunction "2_2") (pintype "passive"))
      (node (ref "C39") (pin "1") (pinfunction "1_1") (pintype "passive"))
      (node (ref "C40") (pin "1") (pinfunction "1_1") (pintype "passive"))
      (node (ref "C41") (pin "2") (pintype "passive"))
      (node (ref "C42") (pin "2") (pintype "passive"))
      (node (ref "DA1") (pin "3") (pinfunction "EMITTER_3") (pintype "passive"))
      (node (ref "DA2") (pin "3") (pinfunction "EMITTER_3") (pintype "passive"))
      (node (ref "DA3") (pin "3") (pinfunction "EMITTER_3") (pintype "passive"))
      (node (ref "DA4") (pin "3") (pinfunction "EMITTER_3") (pintype "passive"))
      (node (ref "DD1") (pin "11") (pinfunction "_GND_11") (pintype "passive"))
      (node (ref "DD1") (pin "20") (pinfunction "_GND_20") (pintype "passive"))
      (node (ref "DD2") (pin "11") (pinfunction "_GND_11") (pintype "passive"))
      (node (ref "DD2") (pin "20") (pinfunction "_GND_20") (pintype "passive"))
      (node (ref "DD3") (pin "11") (pinfunction "_GND_11") (pintype "passive"))
      (node (ref "DD3") (pin "20") (pinfunction "_GND_20") (pintype "passive"))
      (node (ref "DD4") (pin "4") (pinfunction "V-_4") (pintype "passive"))
      (node (ref "DD5") (pin "1") (pinfunction "GND_1") (pintype "passive"))
      (node (ref "TP24") (pin "1") (pinfunction "G9_1") (pintype "passive"))
      (node (ref "X1") (pin "5") (pinfunction "5_5") (pintype "passive"))
    )
    (net (code "30") (name "GNDISO_A") (class "Default")
      (node (ref "C10") (pin "1") (pinfunction "1_1") (pintype "passive"))
      (node (ref "C11") (pin "1") (pinfunction "1_1") (pintype "passive"))
      (node (ref "C16") (pin "1") (pinfunction "1_1") (pintype "passive"))
      (node (ref "C19") (pin "1") (pinfunction "1_1") (pintype "passive"))
      (node (ref "C24") (pin "1") (pinfunction "1_1") (pintype "passive"))
      (node (ref "C25") (pin "1") (pinfunction "1_1") (pintype "passive"))
      (node (ref "C28") (pin "1") (pinfunction "1_1") (pintype "passive"))
      (node (ref "C29") (pin "1") (pinfunction "1_1") (pintype "passive"))
      (node (ref "C3") (pin "1") (pinfunction "1_1") (pintype "passive"))
      (node (ref "C4") (pin "1") (pinfunction "1_1") (pintype "passive"))
      (node (ref "C7") (pin "1") (pinfunction "1_1") (pintype "passive"))
      (node (ref "DD1") (pin "10") (pinfunction "GNDISO_10") (pintype "passive"))
      (node (ref "DD1") (pin "2") (pinfunction "GNDISO_2") (pintype "passive"))
      (node (ref "R21") (pin "2") (pinfunction "2_2") (pintype "passive"))
      (node (ref "R22") (pin "2") (pinfunction "2_2") (pintype "passive"))
      (node (ref "R25") (pin "2") (pinfunction "2_2") (pintype "passive"))
      (node (ref "TP17") (pin "1") (pinfunction "G9_1") (pintype "passive"))
    )
    (net (code "31") (name "GNDISO_B") (class "Default")
      (node (ref "C1") (pin "1") (pinfunction "1_1") (pintype "passive"))
      (node (ref "C14") (pin "1") (pinfunction "1_1") (pintype "passive"))
      (node (ref "C15") (pin "1") (pinfunction "1_1") (pintype "passive"))
      (node (ref "C18") (pin "1") (pinfunction "1_1") (pintype "passive"))
      (node (ref "C2") (pin "1") (pinfunction "1_1") (pintype "passive"))
      (node (ref "C21") (pin "1") (pinfunction "1_1") (pintype "passive"))
      (node (ref "C23") (pin "1") (pinfunction "1_1") (pintype "passive"))
      (node (ref "C27") (pin "1") (pinfunction "1_1") (pintype "passive"))
      (node (ref "C32") (pin "1") (pinfunction "1_1") (pintype "passive"))
      (node (ref "C33") (pin "1") (pinfunction "1_1") (pintype "passive"))
      (node (ref "C9") (pin "1") (pinfunction "1_1") (pintype "passive"))
      (node (ref "DD3") (pin "10") (pinfunction "GNDISO_10") (pintype "passive"))
      (node (ref "DD3") (pin "2") (pinfunction "GNDISO_2") (pintype "passive"))
      (node (ref "R19") (pin "2") (pinfunction "2_2") (pintype "passive"))
      (node (ref "R20") (pin "2") (pinfunction "2_2") (pintype "passive"))
      (node (ref "R27") (pin "2") (pinfunction "2_2") (pintype "passive"))
      (node (ref "TP19") (pin "1") (pinfunction "G9_1") (pintype "passive"))
    )
    (net (code "32") (name "GNDISO_C") (class "Default")
      (node (ref "C12") (pin "1") (pinfunction "1_1") (pintype "passive"))
      (node (ref "C13") (pin "1") (pinfunction "1_1") (pintype "passive"))
      (node (ref "C17") (pin "1") (pinfunction "1_1") (pintype "passive"))
      (node (ref "C20") (pin "1") (pinfunction "1_1") (pintype "passive"))
      (node (ref "C22") (pin "1") (pinfunction "1_1") (pintype "passive"))
      (node (ref "C26") (pin "1") (pinfunction "1_1") (pintype "passive"))
      (node (ref "C30") (pin "1") (pinfunction "1_1") (pintype "passive"))
      (node (ref "C31") (pin "1") (pinfunction "1_1") (pintype "passive"))
      (node (ref "C5") (pin "1") (pinfunction "1_1") (pintype "passive"))
      (node (ref "C6") (pin "1") (pinfunction "1_1") (pintype "passive"))
      (node (ref "C8") (pin "1") (pinfunction "1_1") (pintype "passive"))
      (node (ref "DD2") (pin "10") (pinfunction "GNDISO_10") (pintype "passive"))
      (node (ref "DD2") (pin "2") (pinfunction "GNDISO_2") (pintype "passive"))
      (node (ref "R23") (pin "2") (pinfunction "2_2") (pintype "passive"))
      (node (ref "R24") (pin "2") (pinfunction "2_2") (pintype "passive"))
      (node (ref "R26") (pin "2") (pinfunction "2_2") (pintype "passive"))
      (node (ref "TP18") (pin "1") (pinfunction "G9_1") (pintype "passive"))
    )
    (net (code "33") (name "NEUTRAL") (class "Default")
      (node (ref "DA1") (pin "2") (pinfunction "CATHODE_2") (pintype "passive"))
      (node (ref "DA2") (pin "2") (pinfunction "CATHODE_2") (pintype "passive"))
      (node (ref "DA3") (pin "2") (pinfunction "CATHODE_2") (pintype "passive"))
      (node (ref "DA4") (pin "2") (pinfunction "CATHODE_2") (pintype "passive"))
      (node (ref "DD4") (pin "1") (pinfunction "AC/N_1") (pintype "passive"))
      (node (ref "R2") (pin "2") (pinfunction "2_2") (pintype "passive"))
      (node (ref "R4") (pin "2") (pinfunction "2_2") (pintype "passive"))
      (node (ref "R6") (pin "2") (pinfunction "2_2") (pintype "passive"))
      (node (ref "TP1") (pin "1") (pinfunction "G9_1") (pintype "passive"))
      (node (ref "X5") (pin "5") (pinfunction "5_5") (pintype "passive"))
    )
    (net (code "34") (name "Net-(DA1-ANODE)") (class "Default")
      (node (ref "DA1") (pin "1") (pinfunction "ANODE_1") (pintype "passive"))
      (node (ref "R31") (pin "2") (pinfunction "2_2") (pintype "passive"))
    )
    (net (code "35") (name "Net-(DA2-ANODE)") (class "Default")
      (node (ref "DA2") (pin "1") (pinfunction "ANODE_1") (pintype "passive"))
      (node (ref "R45") (pin "2") (pinfunction "2_2") (pintype "passive"))
    )
    (net (code "36") (name "Net-(DA3-ANODE)") (class "Default")
      (node (ref "DA3") (pin "1") (pinfunction "ANODE_1") (pintype "passive"))
      (node (ref "R46") (pin "2") (pinfunction "2_2") (pintype "passive"))
    )
    (net (code "37") (name "Net-(DA4-ANODE)") (class "Default")
      (node (ref "DA4") (pin "1") (pinfunction "ANODE_1") (pintype "passive"))
      (node (ref "R47") (pin "2") (pinfunction "2_2") (pintype "passive"))
    )
    (net (code "38") (name "Net-(DD1-IM)") (class "Default")
      (node (ref "C10") (pin "2") (pinfunction "2_2") (pintype "passive"))
      (node (ref "DD1") (pin "6") (pinfunction "IM_6") (pintype "passive"))
      (node (ref "R34") (pin "1") (pinfunction "1_1") (pintype "passive"))
      (node (ref "TP14") (pin "1") (pinfunction "G9_1") (pintype "passive"))
      (node (ref "VD27") (pin "1") (pinfunction "C_1") (pintype "passive"))
      (node (ref "VD30") (pin "2") (pinfunction "A_2") (pintype "passive"))
    )
    (net (code "39") (name "Net-(DD1-IP)") (class "Default")
      (node (ref "C11") (pin "2") (pinfunction "2_2") (pintype "passive"))
      (node (ref "DD1") (pin "7") (pinfunction "IP_7") (pintype "passive"))
      (node (ref "R35") (pin "1") (pinfunction "1_1") (pintype "passive"))
      (node (ref "TP15") (pin "1") (pinfunction "G9_1") (pintype "passive"))
      (node (ref "VD27") (pin "2") (pinfunction "A_2") (pintype "passive"))
      (node (ref "VD30") (pin "1") (pinfunction "C_1") (pintype "passive"))
    )
    (net (code "40") (name "Net-(DD1-LDO)") (class "Default")
      (node (ref "C16") (pin "2") (pinfunction "2_2") (pintype "passive"))
      (node (ref "C19") (pin "2") (pinfunction "2_2") (pintype "passive"))
      (node (ref "DD1") (pin "8") (pinfunction "LDO_8") (pintype "passive"))
    )
    (net (code "41") (name "Net-(DD1-REF)") (class "Default")
      (node (ref "C25") (pin "2") (pinfunction "2_2") (pintype "passive"))
      (node (ref "C29") (pin "2") (pinfunction "2_2") (pintype "passive"))
      (node (ref "DD1") (pin "9") (pinfunction "REF_9") (pintype "passive"))
    )
    (net (code "42") (name "Net-(DD1-VDDISO)") (class "Default")
      (node (ref "C24") (pin "2") (pinfunction "2_2") (pintype "passive"))
      (node (ref "C28") (pin "2") (pinfunction "2_2") (pintype "passive"))
      (node (ref "DD1") (pin "1") (pinfunction "VDDISO_1") (pintype "passive"))
      (node (ref "TP22") (pin "1") (pinfunction "G9_1") (pintype "passive"))
    )
    (net (code "43") (name "Net-(DD1-XTAL1)") (class "Default")
      (node (ref "DD1") (pin "13") (pinfunction "XTAL1_13") (pintype "passive"))
      (node (ref "DD2") (pin "13") (pinfunction "XTAL1_13") (pintype "passive"))
      (node (ref "DD3") (pin "12") (pinfunction "CLKOUT/DREADY_12") (pintype "passive"))
    )
    (net (code "44") (name "Net-(DD2-IM)") (class "Default")
      (node (ref "C12") (pin "2") (pinfunction "2_2") (pintype "passive"))
      (node (ref "DD2") (pin "6") (pinfunction "IM_6") (pintype "passive"))
      (node (ref "R36") (pin "1") (pinfunction "1_1") (pintype "passive"))
      (node (ref "TP16") (pin "1") (pinfunction "G9_1") (pintype "passive"))
      (node (ref "VD25") (pin "1") (pinfunction "C_1") (pintype "passive"))
      (node (ref "VD28") (pin "2") (pinfunction "A_2") (pintype "passive"))
    )
    (net (code "45") (name "Net-(DD2-IP)") (class "Default")
      (node (ref "C13") (pin "2") (pinfunction "2_2") (pintype "passive"))
      (node (ref "DD2") (pin "7") (pinfunction "IP_7") (pintype "passive"))
      (node (ref "R37") (pin "1") (pinfunction "1_1") (pintype "passive"))
      (node (ref "TP11") (pin "1") (pinfunction "G9_1") (pintype "passive"))
      (node (ref "VD25") (pin "2") (pinfunction "A_2") (pintype "passive"))
      (node (ref "VD28") (pin "1") (pinfunction "C_1") (pintype "passive"))
    )
    (net (code "46") (name "Net-(DD2-LDO)") (class "Default")
      (node (ref "C17") (pin "2") (pinfunction "2_2") (pintype "passive"))
      (node (ref "C20") (pin "2") (pinfunction "2_2") (pintype "passive"))
      (node (ref "DD2") (pin "8") (pinfunction "LDO_8") (pintype "passive"))
    )
    (net (code "47") (name "Net-(DD2-REF)") (class "Default")
      (node (ref "C26") (pin "2") (pinfunction "2_2") (pintype "passive"))
      (node (ref "C31") (pin "2") (pinfunction "2_2") (pintype "passive"))
      (node (ref "DD2") (pin "9") (pinfunction "REF_9") (pintype "passive"))
    )
    (net (code "48") (name "Net-(DD2-VDDISO)") (class "Default")
      (node (ref "C22") (pin "2") (pinfunction "2_2") (pintype "passive"))
      (node (ref "C30") (pin "2") (pinfunction "2_2") (pintype "passive"))
      (node (ref "DD2") (pin "1") (pinfunction "VDDISO_1") (pintype "passive"))
      (node (ref "TP21") (pin "1") (pinfunction "G9_1") (pintype "passive"))
    )
    (net (code "49") (name "Net-(DD3-IM)") (class "Default")
      (node (ref "C14") (pin "2") (pinfunction "2_2") (pintype "passive"))
      (node (ref "DD3") (pin "6") (pinfunction "IM_6") (pintype "passive"))
      (node (ref "R38") (pin "1") (pinfunction "1_1") (pintype "passive"))
      (node (ref "TP12") (pin "1") (pinfunction "G9_1") (pintype "passive"))
      (node (ref "VD26") (pin "1") (pinfunction "C_1") (pintype "passive"))
      (node (ref "VD29") (pin "2") (pinfunction "A_2") (pintype "passive"))
    )
    (net (code "50") (name "Net-(DD3-IP)") (class "Default")
      (node (ref "C15") (pin "2") (pinfunction "2_2") (pintype "passive"))
      (node (ref "DD3") (pin "7") (pinfunction "IP_7") (pintype "passive"))
      (node (ref "R39") (pin "1") (pinfunction "1_1") (pintype "passive"))
      (node (ref "TP13") (pin "1") (pinfunction "G9_1") (pintype "passive"))
      (node (ref "VD26") (pin "2") (pinfunction "A_2") (pintype "passive"))
      (node (ref "VD29") (pin "1") (pinfunction "C_1") (pintype "passive"))
    )
    (net (code "51") (name "Net-(DD3-LDO)") (class "Default")
      (node (ref "C18") (pin "2") (pinfunction "2_2") (pintype "passive"))
      (node (ref "C21") (pin "2") (pinfunction "2_2") (pintype "passive"))
      (node (ref "DD3") (pin "8") (pinfunction "LDO_8") (pintype "passive"))
    )
    (net (code "52") (name "Net-(DD3-REF)") (class "Default")
      (node (ref "C27") (pin "2") (pinfunction "2_2") (pintype "passive"))
      (node (ref "C33") (pin "2") (pinfunction "2_2") (pintype "passive"))
      (node (ref "DD3") (pin "9") (pinfunction "REF_9") (pintype "passive"))
    )
    (net (code "53") (name "Net-(DD3-VDDISO)") (class "Default")
      (node (ref "C23") (pin "2") (pinfunction "2_2") (pintype "passive"))
      (node (ref "C32") (pin "2") (pinfunction "2_2") (pintype "passive"))
      (node (ref "DD3") (pin "1") (pinfunction "VDDISO_1") (pintype "passive"))
      (node (ref "TP20") (pin "1") (pinfunction "G9_1") (pintype "passive"))
    )
    (net (code "54") (name "Net-(DD3-XTAL1)") (class "Default")
      (node (ref "C34") (pin "2") (pinfunction "2_2") (pintype "passive"))
      (node (ref "DD3") (pin "13") (pinfunction "XTAL1_13") (pintype "passive"))
      (node (ref "Q1") (pin "1") (pinfunction "1_1") (pintype "passive"))
    )
    (net (code "55") (name "Net-(DD3-XTAL2)") (class "Default")
      (node (ref "C35") (pin "2") (pinfunction "2_2") (pintype "passive"))
      (node (ref "DD3") (pin "14") (pinfunction "XTAL2_14") (pintype "passive"))
      (node (ref "Q1") (pin "2") (pinfunction "2_2") (pintype "passive"))
    )
    (net (code "56") (name "Net-(R1-Pad1)") (class "Default")
      (node (ref "R1") (pin "1") (pinfunction "1_1") (pintype "passive"))
      (node (ref "R7") (pin "2") (pinfunction "2_2") (pintype "passive"))
    )
    (net (code "57") (name "Net-(R2-Pad1)") (class "Default")
      (node (ref "R2") (pin "1") (pinfunction "1_1") (pintype "passive"))
      (node (ref "R8") (pin "2") (pinfunction "2_2") (pintype "passive"))
    )
    (net (code "58") (name "Net-(R3-Pad1)") (class "Default")
      (node (ref "R3") (pin "1") (pinfunction "1_1") (pintype "passive"))
      (node (ref "R9") (pin "2") (pinfunction "2_2") (pintype "passive"))
    )
    (net (code "59") (name "Net-(R10-Pad1)") (class "Default")
      (node (ref "R10") (pin "1") (pinfunction "1_1") (pintype "passive"))
      (node (ref "R16") (pin "2") (pinfunction "2_2") (pintype "passive"))
    )
    (net (code "60") (name "Net-(R10-Pad2)") (class "Default")
      (node (ref "R10") (pin "2") (pinfunction "2_2") (pintype "passive"))
      (node (ref "R4") (pin "1") (pinfunction "1_1") (pintype "passive"))
    )
    (net (code "61") (name "Net-(R11-Pad1)") (class "Default")
      (node (ref "R11") (pin "1") (pinfunction "1_1") (pintype "passive"))
      (node (ref "R17") (pin "2") (pinfunction "2_2") (pintype "passive"))
    )
    (net (code "62") (name "Net-(R11-Pad2)") (class "Default")
      (node (ref "R11") (pin "2") (pinfunction "2_2") (pintype "passive"))
      (node (ref "R5") (pin "1") (pinfunction "1_1") (pintype "passive"))
    )
    (net (code "63") (name "Net-(R12-Pad1)") (class "Default")
      (node (ref "R12") (pin "1") (pinfunction "1_1") (pintype "passive"))
      (node (ref "R18") (pin "2") (pinfunction "2_2") (pintype "passive"))
    )
    (net (code "64") (name "Net-(R12-Pad2)") (class "Default")
      (node (ref "R12") (pin "2") (pinfunction "2_2") (pintype "passive"))
      (node (ref "R6") (pin "1") (pinfunction "1_1") (pintype "passive"))
    )
    (net (code "65") (name "Net-(R13-Pad2)") (class "Default")
      (node (ref "R13") (pin "2") (pinfunction "2_2") (pintype "passive"))
      (node (ref "R7") (pin "1") (pinfunction "1_1") (pintype "passive"))
    )
    (net (code "66") (name "Net-(R14-Pad2)") (class "Default")
      (node (ref "R14") (pin "2") (pinfunction "2_2") (pintype "passive"))
      (node (ref "R8") (pin "1") (pinfunction "1_1") (pintype "passive"))
    )
    (net (code "67") (name "Net-(R15-Pad2)") (class "Default")
      (node (ref "R15") (pin "2") (pinfunction "2_2") (pintype "passive"))
      (node (ref "R9") (pin "1") (pinfunction "1_1") (pintype "passive"))
    )
    (net (code "68") (name "Net-(R28-Pad1)") (class "Default")
      (node (ref "R28") (pin "1") (pinfunction "1_1") (pintype "passive"))
      (node (ref "R30") (pin "1") (pinfunction "1_1") (pintype "passive"))
    )
    (net (code "69") (name "Net-(R30-Pad2)") (class "Default")
      (node (ref "R30") (pin "2") (pinfunction "2_2") (pintype "passive"))
      (node (ref "R31") (pin "1") (pinfunction "1_1") (pintype "passive"))
    )
    (net (code "70") (name "Net-(R32-Pad2)") (class "Default")
      (node (ref "R32") (pin "2") (pinfunction "2_2") (pintype "passive"))
      (node (ref "R42") (pin "1") (pinfunction "1_1") (pintype "passive"))
    )
    (net (code "71") (name "Net-(R33-Pad2)") (class "Default")
      (node (ref "R33") (pin "2") (pinfunction "2_2") (pintype "passive"))
      (node (ref "R43") (pin "1") (pinfunction "1_1") (pintype "passive"))
    )
    (net (code "72") (name "Net-(R41-Pad2)") (class "Default")
      (node (ref "R41") (pin "2") (pinfunction "2_2") (pintype "passive"))
      (node (ref "R44") (pin "1") (pinfunction "1_1") (pintype "passive"))
    )
    (net (code "73") (name "Net-(R42-Pad2)") (class "Default")
      (node (ref "R42") (pin "2") (pinfunction "2_2") (pintype "passive"))
      (node (ref "R45") (pin "1") (pinfunction "1_1") (pintype "passive"))
    )
    (net (code "74") (name "Net-(R43-Pad2)") (class "Default")
      (node (ref "R43") (pin "2") (pinfunction "2_2") (pintype "passive"))
      (node (ref "R46") (pin "1") (pinfunction "1_1") (pintype "passive"))
    )
    (net (code "75") (name "Net-(R44-Pad2)") (class "Default")
      (node (ref "R44") (pin "2") (pinfunction "2_2") (pintype "passive"))
      (node (ref "R47") (pin "1") (pinfunction "1_1") (pintype "passive"))
    )
    (net (code "76") (name "Net-(VD1-C)") (class "Default")
      (node (ref "VD1") (pin "1") (pinfunction "C_1") (pintype "passive"))
      (node (ref "VD2") (pin "2") (pinfunction "A_2") (pintype "passive"))
    )
    (net (code "77") (name "Net-(VD3-C)") (class "Default")
      (node (ref "VD3") (pin "1") (pinfunction "C_1") (pintype "passive"))
      (node (ref "VD4") (pin "2") (pinfunction "A_2") (pintype "passive"))
    )
    (net (code "78") (name "Net-(VD5-C)") (class "Default")
      (node (ref "VD5") (pin "1") (pinfunction "C_1") (pintype "passive"))
      (node (ref "VD6") (pin "2") (pinfunction "A_2") (pintype "passive"))
    )
    (net (code "79") (name "Net-(VD7-C)") (class "Default")
      (node (ref "VD7") (pin "1") (pinfunction "C_1") (pintype "passive"))
      (node (ref "VD8") (pin "2") (pinfunction "A_2") (pintype "passive"))
    )
    (net (code "80") (name "Net-(VD10-A)") (class "Default")
      (node (ref "VD10") (pin "2") (pinfunction "A_2") (pintype "passive"))
      (node (ref "VD9") (pin "1") (pinfunction "C_1") (pintype "passive"))
    )
    (net (code "81") (name "Net-(VD11-C)") (class "Default")
      (node (ref "VD11") (pin "1") (pinfunction "C_1") (pintype "passive"))
      (node (ref "VD12") (pin "2") (pinfunction "A_2") (pintype "passive"))
    )
    (net (code "82") (name "Net-(VD13-A)") (class "Default")
      (node (ref "VD13") (pin "2") (pinfunction "A_2") (pintype "passive"))
      (node (ref "VD14") (pin "1") (pinfunction "C_1") (pintype "passive"))
    )
    (net (code "83") (name "Net-(VD15-A)") (class "Default")
      (node (ref "VD15") (pin "2") (pinfunction "A_2") (pintype "passive"))
      (node (ref "VD16") (pin "1") (pinfunction "C_1") (pintype "passive"))
    )
    (net (code "84") (name "Net-(VD17-A)") (class "Default")
      (node (ref "VD17") (pin "2") (pinfunction "A_2") (pintype "passive"))
      (node (ref "VD18") (pin "1") (pinfunction "C_1") (pintype "passive"))
    )
    (net (code "85") (name "Net-(VD19-A)") (class "Default")
      (node (ref "VD19") (pin "2") (pinfunction "A_2") (pintype "passive"))
      (node (ref "VD20") (pin "1") (pinfunction "C_1") (pintype "passive"))
    )
    (net (code "86") (name "Net-(VD21-A)") (class "Default")
      (node (ref "VD21") (pin "2") (pinfunction "A_2") (pintype "passive"))
      (node (ref "VD22") (pin "1") (pinfunction "C_1") (pintype "passive"))
    )
    (net (code "87") (name "Net-(VD23-A)") (class "Default")
      (node (ref "VD23") (pin "2") (pinfunction "A_2") (pintype "passive"))
      (node (ref "VD24") (pin "1") (pinfunction "C_1") (pintype "passive"))
    )
    (net (code "88") (name "PS") (class "Default")
      (node (ref "DA1") (pin "4") (pinfunction "COLLECTOR_4") (pintype "passive"))
      (node (ref "R29") (pin "2") (pinfunction "2_2") (pintype "passive"))
      (node (ref "X2") (pin "1") (pinfunction "1_1") (pintype "passive"))
    )
    (net (code "89") (name "unconnected-(DD1-XTAL2-Pad14)") (class "Default")
      (node (ref "DD1") (pin "14") (pinfunction "XTAL2_14") (pintype "passive"))
    )
    (net (code "90") (name "unconnected-(DD2-CLKOUT{slash}DREADY-Pad12)") (class "Default")
      (node (ref "DD2") (pin "12") (pinfunction "CLKOUT/DREADY_12") (pintype "passive"))
    )
    (net (code "91") (name "unconnected-(DD2-XTAL2-Pad14)") (class "Default")
      (node (ref "DD2") (pin "14") (pinfunction "XTAL2_14") (pintype "passive"))
    )
    (net (code "92") (name "unconnected-(X2-Pad5)") (class "Default")
      (node (ref "X2") (pin "5") (pinfunction "5_5") (pintype "passive"))
    )
    (net (code "93") (name "unconnected-(X3-Pad1)") (class "Default")
      (node (ref "X3") (pin "1") (pinfunction "1_1") (pintype "passive"))
    )
    (net (code "94") (name "unconnected-(X3-Pad2)") (class "Default")
      (node (ref "X3") (pin "2") (pinfunction "2_2") (pintype "passive"))
    )
    (net (code "95") (name "unconnected-(X3-Pad4)") (class "Default")
      (node (ref "X3") (pin "4") (pinfunction "4_4") (pintype "passive"))
    )
    (net (code "96") (name "unconnected-(X3-Pad5)") (class "Default")
      (node (ref "X3") (pin "5") (pinfunction "5_5") (pintype "passive"))
    )
    (net (code "97") (name "unconnected-(X4-Pad3)") (class "Default")
      (node (ref "X4") (pin "3") (pinfunction "3_3") (pintype "passive"))
    )
    (net (code "98") (name "unconnected-(X5-Pad1)") (class "Default")
      (node (ref "X5") (pin "1") (pinfunction "1_1") (pintype "passive"))
    )
    (net (code "99") (name "unconnected-(X5-Pad4)") (class "Default")
      (node (ref "X5") (pin "4") (pinfunction "4_4") (pintype "passive"))
    )
  )
)
